# CAP-SENSE-SLIM.net
KiCad netlist of a schematic drawn in EAGLE
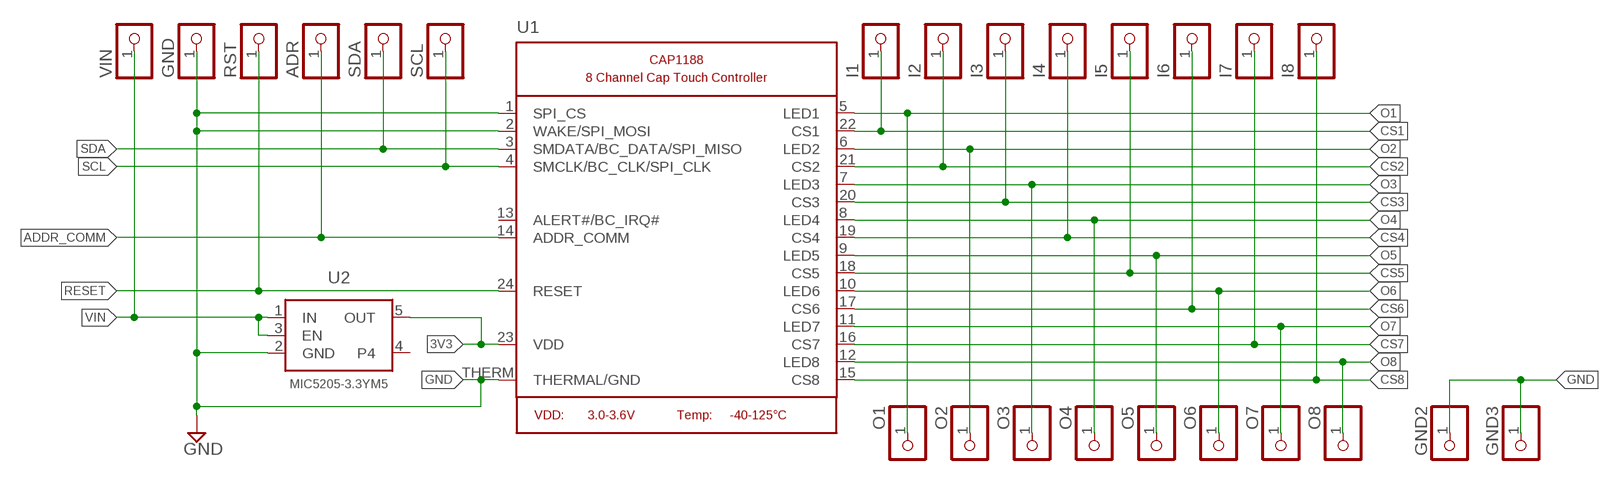
[diagram p0: schematic, sheet 1]

(export (version "E")
  (design (tool "Eeschema 10.0.6"))
  (components
    (comp (ref "ADR")
      (value "PINHD-1X1CB")
      (footprint "eagle-import:1X01-CLEANBIG")
      (libsource (lib "eagle-import") (part "PINHD-1X1CB"))
    )
    (comp (ref "GND")
      (value "PINHD-1X1CB")
      (footprint "eagle-import:1X01-CLEANBIG")
      (libsource (lib "eagle-import") (part "PINHD-1X1CB"))
    )
    (comp (ref "GND2")
      (value "PINHD-1X1CB")
      (footprint "eagle-import:1X01-CLEANBIG")
      (libsource (lib "eagle-import") (part "PINHD-1X1CB"))
    )
    (comp (ref "GND3")
      (value "PINHD-1X1CB")
      (footprint "eagle-import:1X01-CLEANBIG")
      (libsource (lib "eagle-import") (part "PINHD-1X1CB"))
    )
    (comp (ref "I1")
      (value "PINHD-1X1CB")
      (footprint "eagle-import:1X01-CLEANBIG")
      (libsource (lib "eagle-import") (part "PINHD-1X1CB"))
    )
    (comp (ref "I2")
      (value "PINHD-1X1CB")
      (footprint "eagle-import:1X01-CLEANBIG")
      (libsource (lib "eagle-import") (part "PINHD-1X1CB"))
    )
    (comp (ref "I3")
      (value "PINHD-1X1CB")
      (footprint "eagle-import:1X01-CLEANBIG")
      (libsource (lib "eagle-import") (part "PINHD-1X1CB"))
    )
    (comp (ref "I4")
      (value "PINHD-1X1CB")
      (footprint "eagle-import:1X01-CLEANBIG")
      (libsource (lib "eagle-import") (part "PINHD-1X1CB"))
    )
    (comp (ref "I5")
      (value "PINHD-1X1CB")
      (footprint "eagle-import:1X01-CLEANBIG")
      (libsource (lib "eagle-import") (part "PINHD-1X1CB"))
    )
    (comp (ref "I6")
      (value "PINHD-1X1CB")
      (footprint "eagle-import:1X01-CLEANBIG")
      (libsource (lib "eagle-import") (part "PINHD-1X1CB"))
    )
    (comp (ref "I7")
      (value "PINHD-1X1CB")
      (footprint "eagle-import:1X01-CLEANBIG")
      (libsource (lib "eagle-import") (part "PINHD-1X1CB"))
    )
    (comp (ref "I8")
      (value "PINHD-1X1CB")
      (footprint "eagle-import:1X01-CLEANBIG")
      (libsource (lib "eagle-import") (part "PINHD-1X1CB"))
    )
    (comp (ref "O1")
      (value "PINHD-1X1CB")
      (footprint "eagle-import:1X01-CLEANBIG")
      (libsource (lib "eagle-import") (part "PINHD-1X1CB"))
    )
    (comp (ref "O2")
      (value "PINHD-1X1CB")
      (footprint "eagle-import:1X01-CLEANBIG")
      (libsource (lib "eagle-import") (part "PINHD-1X1CB"))
    )
    (comp (ref "O3")
      (value "PINHD-1X1CB")
      (footprint "eagle-import:1X01-CLEANBIG")
      (libsource (lib "eagle-import") (part "PINHD-1X1CB"))
    )
    (comp (ref "O4")
      (value "PINHD-1X1CB")
      (footprint "eagle-import:1X01-CLEANBIG")
      (libsource (lib "eagle-import") (part "PINHD-1X1CB"))
    )
    (comp (ref "O5")
      (value "PINHD-1X1CB")
      (footprint "eagle-import:1X01-CLEANBIG")
      (libsource (lib "eagle-import") (part "PINHD-1X1CB"))
    )
    (comp (ref "O6")
      (value "PINHD-1X1CB")
      (footprint "eagle-import:1X01-CLEANBIG")
      (libsource (lib "eagle-import") (part "PINHD-1X1CB"))
    )
    (comp (ref "O7")
      (value "PINHD-1X1CB")
      (footprint "eagle-import:1X01-CLEANBIG")
      (libsource (lib "eagle-import") (part "PINHD-1X1CB"))
    )
    (comp (ref "O8")
      (value "PINHD-1X1CB")
      (footprint "eagle-import:1X01-CLEANBIG")
      (libsource (lib "eagle-import") (part "PINHD-1X1CB"))
    )
    (comp (ref "RST")
      (value "PINHD-1X1CB")
      (footprint "eagle-import:1X01-CLEANBIG")
      (libsource (lib "eagle-import") (part "PINHD-1X1CB"))
    )
    (comp (ref "SCL")
      (value "PINHD-1X1CB")
      (footprint "eagle-import:1X01-CLEANBIG")
      (libsource (lib "eagle-import") (part "PINHD-1X1CB"))
    )
    (comp (ref "SDA")
      (value "PINHD-1X1CB")
      (footprint "eagle-import:1X01-CLEANBIG")
      (libsource (lib "eagle-import") (part "PINHD-1X1CB"))
    )
    (comp (ref "U1")
      (value "MICROBUILDER_CAP1188")
      (footprint "eagle-import:MICROBUILDER_QFN24_4MM_SMSC")
      (libsource (lib "eagle-import") (part "MICROBUILDER_CAP1188"))
    )
    (comp (ref "U2")
      (value "MIC5205-3.3YM5")
      (footprint "eagle-import:MICROBUILDER_SOT23-5")
      (libsource (lib "eagle-import") (part "MICROBUILDER_VREG_SOT23-5"))
    )
    (comp (ref "VIN")
      (value "PINHD-1X1CB")
      (footprint "eagle-import:1X01-CLEANBIG")
      (libsource (lib "eagle-import") (part "PINHD-1X1CB"))
    )
  )
  (nets
    (net (code "1") (name "3V3") (class "Default")
      (node (ref "U1") (pin "23") (pinfunction "VDD_23") (pintype "power_in"))
      (node (ref "U2") (pin "5") (pinfunction "OUT_5") (pintype "power_in"))
    )
    (net (code "2") (name "ADDR_COMM") (class "Default")
      (node (ref "ADR") (pin "1") (pinfunction "1_1") (pintype "passive"))
      (node (ref "U1") (pin "14") (pinfunction "ADDR_COMM_14") (pintype "bidirectional"))
    )
    (net (code "3") (name "CS1") (class "Default")
      (node (ref "I1") (pin "1") (pinfunction "1_1") (pintype "passive"))
      (node (ref "U1") (pin "22") (pinfunction "CS1_22") (pintype "bidirectional"))
    )
    (net (code "4") (name "CS2") (class "Default")
      (node (ref "I2") (pin "1") (pinfunction "1_1") (pintype "passive"))
      (node (ref "U1") (pin "21") (pinfunction "CS2_21") (pintype "bidirectional"))
    )
    (net (code "5") (name "CS3") (class "Default")
      (node (ref "I3") (pin "1") (pinfunction "1_1") (pintype "passive"))
      (node (ref "U1") (pin "20") (pinfunction "CS3_20") (pintype "bidirectional"))
    )
    (net (code "6") (name "CS4") (class "Default")
      (node (ref "I4") (pin "1") (pinfunction "1_1") (pintype "passive"))
      (node (ref "U1") (pin "19") (pinfunction "CS4_19") (pintype "bidirectional"))
    )
    (net (code "7") (name "CS5") (class "Default")
      (node (ref "I5") (pin "1") (pinfunction "1_1") (pintype "passive"))
      (node (ref "U1") (pin "18") (pinfunction "CS5_18") (pintype "bidirectional"))
    )
    (net (code "8") (name "CS6") (class "Default")
      (node (ref "I6") (pin "1") (pinfunction "1_1") (pintype "passive"))
      (node (ref "U1") (pin "17") (pinfunction "CS6_17") (pintype "bidirectional"))
    )
    (net (code "9") (name "CS7") (class "Default")
      (node (ref "I7") (pin "1") (pinfunction "1_1") (pintype "passive"))
      (node (ref "U1") (pin "16") (pinfunction "CS7_16") (pintype "bidirectional"))
    )
    (net (code "10") (name "CS8") (class "Default")
      (node (ref "I8") (pin "1") (pinfunction "1_1") (pintype "passive"))
      (node (ref "U1") (pin "15") (pinfunction "CS8_15") (pintype "bidirectional"))
    )
    (net (code "11") (name "GND") (class "Default")
      (node (ref "GND") (pin "1") (pinfunction "1_1") (pintype "passive"))
      (node (ref "GND2") (pin "1") (pinfunction "1_1") (pintype "passive"))
      (node (ref "GND3") (pin "1") (pinfunction "1_1") (pintype "passive"))
      (node (ref "U1") (pin "1") (pinfunction "SPI_CS_1") (pintype "input"))
      (node (ref "U1") (pin "2") (pinfunction "WAKE/SPI_MOSI_2") (pintype "bidirectional"))
      (node (ref "U1") (pin "THERM") (pinfunction "THERMAL/GND_THERM") (pintype "power_in"))
      (node (ref "U2") (pin "2") (pinfunction "GND_2") (pintype "power_in"))
    )
    (net (code "12") (name "O1") (class "Default")
      (node (ref "O1") (pin "1") (pinfunction "1_1") (pintype "passive"))
      (node (ref "U1") (pin "5") (pinfunction "LED1_5") (pintype "bidirectional"))
    )
    (net (code "13") (name "O2") (class "Default")
      (node (ref "O2") (pin "1") (pinfunction "1_1") (pintype "passive"))
      (node (ref "U1") (pin "6") (pinfunction "LED2_6") (pintype "bidirectional"))
    )
    (net (code "14") (name "O3") (class "Default")
      (node (ref "O3") (pin "1") (pinfunction "1_1") (pintype "passive"))
      (node (ref "U1") (pin "7") (pinfunction "LED3_7") (pintype "bidirectional"))
    )
    (net (code "15") (name "O4") (class "Default")
      (node (ref "O4") (pin "1") (pinfunction "1_1") (pintype "passive"))
      (node (ref "U1") (pin "8") (pinfunction "LED4_8") (pintype "bidirectional"))
    )
    (net (code "16") (name "O5") (class "Default")
      (node (ref "O5") (pin "1") (pinfunction "1_1") (pintype "passive"))
      (node (ref "U1") (pin "9") (pinfunction "LED5_9") (pintype "bidirectional"))
    )
    (net (code "17") (name "O6") (class "Default")
      (node (ref "O6") (pin "1") (pinfunction "1_1") (pintype "passive"))
      (node (ref "U1") (pin "10") (pinfunction "LED6_10") (pintype "bidirectional"))
    )
    (net (code "18") (name "O7") (class "Default")
      (node (ref "O7") (pin "1") (pinfunction "1_1") (pintype "passive"))
      (node (ref "U1") (pin "11") (pinfunction "LED7_11") (pintype "bidirectional"))
    )
    (net (code "19") (name "O8") (class "Default")
      (node (ref "O8") (pin "1") (pinfunction "1_1") (pintype "passive"))
      (node (ref "U1") (pin "12") (pinfunction "LED8_12") (pintype "bidirectional"))
    )
    (net (code "20") (name "RESET") (class "Default")
      (node (ref "RST") (pin "1") (pinfunction "1_1") (pintype "passive"))
      (node (ref "U1") (pin "24") (pinfunction "RESET_24") (pintype "input"))
    )
    (net (code "21") (name "SCL") (class "Default")
      (node (ref "SCL") (pin "1") (pinfunction "1_1") (pintype "passive"))
      (node (ref "U1") (pin "4") (pinfunction "SMCLK/BC_CLK/SPI_CLK_4") (pintype "bidirectional"))
    )
    (net (code "22") (name "SDA") (class "Default")
      (node (ref "SDA") (pin "1") (pinfunction "1_1") (pintype "passive"))
      (node (ref "U1") (pin "3") (pinfunction "SMDATA/BC_DATA/SPI_MISO_3") (pintype "bidirectional"))
    )
    (net (code "23") (name "VIN") (class "Default")
      (node (ref "U2") (pin "1") (pinfunction "IN_1") (pintype "power_in"))
      (node (ref "U2") (pin "3") (pinfunction "EN_3") (pintype "input"))
      (node (ref "VIN") (pin "1") (pinfunction "1_1") (pintype "passive"))
    )
    (net (code "24") (name "unconnected-(U1-ALERT#{slash}BC_IRQ#-Pad13)") (class "Default")
      (node (ref "U1") (pin "13") (pinfunction "ALERT#/BC_IRQ#_13") (pintype "bidirectional"))
    )
    (net (code "25") (name "unconnected-(U2-P4-Pad4)") (class "Default")
      (node (ref "U2") (pin "4") (pinfunction "P4_4") (pintype "bidirectional"))
    )
  )
)
